# SUPPLY.net
KiCad netlist of a schematic drawn in Altium Designer
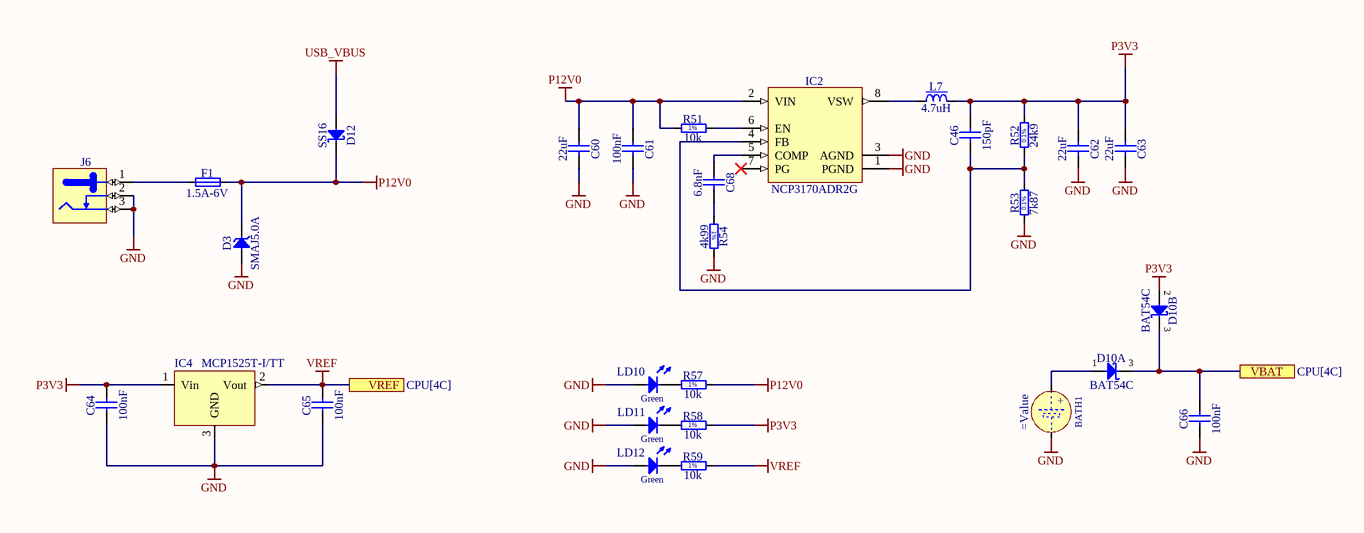
[diagram p0: SUPPLY.SchDoc]

(export (version "E")
  (design (tool "Eeschema 10.0.6"))
  (components
    (comp (ref "BATH1")
      (value "~")
      (footprint "BATH_KEYSTONE_2998")
      (description "Battery Holder whit 2 Pin")
      (fields
        (field (name "PART NUMBER") "BATH_KEYSTONE_2998")
        (field (name "MANUFACTURER") "KEYSTONE")
        (field (name "AUTHOR") "CERN DEM JLC")
      )
      (libsource (lib "Eletro-mechanical") (part "Battery Holder 2 Pin"))
    )
    (comp (ref "C46")
      (value "150pF")
      (footprint "CAPC1005X55N")
      (description "Non-polarised capacitor")
      (fields
        (field (name "PART NUMBER") "CC0402_150PF_50V_5%_C0G")
        (field (name "VOLTAGE") "50V")
        (field (name "AUTHOR") "CERN DEM JLC")
      )
      (libsource (lib "Capacitors") (part "Capacitor - non polarized"))
    )
    (comp (ref "C60")
      (value "22uF")
      (footprint "CAPC2012X135N")
      (description "Non-polarised capacitor")
      (fields
        (field (name "PART NUMBER") "CC0805_22UF_16V_10%_X5R")
        (field (name "VOLTAGE") "16V")
        (field (name "AUTHOR") "CERN DEM JLC")
      )
      (libsource (lib "Capacitors") (part "Capacitor - non polarized"))
    )
    (comp (ref "C61")
      (value "100nF")
      (footprint "CAPC1005X55N")
      (description "Non-polarised capacitor")
      (fields
        (field (name "PART NUMBER") "CC0402_100NF_16V_10%_X5R")
        (field (name "VOLTAGE") "16V")
        (field (name "AUTHOR") "CERN DEM JLC")
      )
      (libsource (lib "Capacitors") (part "Capacitor - non polarized"))
    )
    (comp (ref "C62")
      (value "22uF")
      (footprint "CAPC2012X135N")
      (description "Non-polarised capacitor")
      (fields
        (field (name "PART NUMBER") "CC0805_22UF_16V_10%_X5R")
        (field (name "VOLTAGE") "16V")
        (field (name "AUTHOR") "CERN DEM JLC")
      )
      (libsource (lib "Capacitors") (part "Capacitor - non polarized"))
    )
    (comp (ref "C63")
      (value "22uF")
      (footprint "CAPC2012X135N")
      (description "Non-polarised capacitor")
      (fields
        (field (name "PART NUMBER") "CC0805_22UF_16V_10%_X5R")
        (field (name "VOLTAGE") "16V")
        (field (name "AUTHOR") "CERN DEM JLC")
      )
      (libsource (lib "Capacitors") (part "Capacitor - non polarized"))
    )
    (comp (ref "C64")
      (value "100nF")
      (footprint "CAPC1005X55N")
      (description "Non-polarised capacitor")
      (fields
        (field (name "PART NUMBER") "CC0402_100NF_16V_10%_X5R")
        (field (name "VOLTAGE") "16V")
        (field (name "AUTHOR") "CERN DEM JLC")
      )
      (libsource (lib "Capacitors") (part "Capacitor - non polarized"))
    )
    (comp (ref "C65")
      (value "100nF")
      (footprint "CAPC1005X55N")
      (description "Non-polarised capacitor")
      (fields
        (field (name "PART NUMBER") "CC0402_100NF_16V_10%_X5R")
        (field (name "VOLTAGE") "16V")
        (field (name "AUTHOR") "CERN DEM JLC")
      )
      (libsource (lib "Capacitors") (part "Capacitor - non polarized"))
    )
    (comp (ref "C66")
      (value "100nF")
      (footprint "CAPC1005X55N")
      (description "Non-polarised capacitor")
      (fields
        (field (name "PART NUMBER") "CC0402_100NF_16V_10%_X5R")
        (field (name "VOLTAGE") "16V")
        (field (name "AUTHOR") "CERN DEM JLC")
      )
      (libsource (lib "Capacitors") (part "Capacitor - non polarized"))
    )
    (comp (ref "C68")
      (value "6.8nF")
      (footprint "CAPC1608X87N")
      (description "Non-polarised capacitor")
      (fields
        (field (name "PART NUMBER") "CC0603_6.8NF_50V_5%_X7R")
        (field (name "VOLTAGE") "50V")
        (field (name "AUTHOR") "CERN DEM JLC")
      )
      (libsource (lib "Capacitors") (part "Capacitor - non polarized"))
    )
    (comp (ref "D3")
      (value "SMAJ5.0A")
      (footprint "DIOM5226X262N")
      (description "Transient Voltage Suppressor Diode (Uni-Directional)")
      (fields
        (field (name "VOLTAGE") "5V")
        (field (name "POWER") "400W")
        (field (name "AUTHOR") "CERN DEM MR")
      )
      (libsource (lib "ICs And Semiconductors") (part "Diode TVS Uni-Directional"))
    )
    (comp (ref "D10")
      (value "BAT54C")
      (footprint "SOT95P240X130-3N")
      (description "Dual Common Cathode Schottky Diodes")
      (fields
        (field (name "VOLTAGE") "30V")
        (field (name "POWER") "200mA")
        (field (name "AUTHOR") "CERN DEM JLC")
      )
      (libsource (lib "ICs And Semiconductors") (part "Diode Schottky x2 A1C3_A2C3"))
    )
    (comp (ref "D12")
      (value "SS16")
      (footprint "DIOM5127X229N")
      (description "Schottky Diode")
      (fields
        (field (name "VOLTAGE") "60V")
        (field (name "POWER") "1A")
        (field (name "AUTHOR") "CERN DEM JLC")
      )
      (libsource (lib "ICs And Semiconductors") (part "Diode Schottky"))
    )
    (comp (ref "F1")
      (value "1.5A-6V")
      (footprint "FUSRC4632X90N")
      (description "Fuse")
      (fields
        (field (name "PART NUMBER") "FUSR1812_TYCO-MINISMDC150F-2")
        (field (name "MANUFACTURER") "TYCO ELECTRONICS")
        (field (name "AUTHOR") "CERN DEM MR")
      )
      (libsource (lib "Eletro-mechanical") (part "Fuse"))
    )
    (comp (ref "IC2")
      (value "NCP3170ADR2G")
      (footprint "SOIC127P600X175-8N")
      (description "Synchronous PWM Switching Converter")
      (fields (field (name "MANUFACTURER") "ON SEMICONDUCTOR") (field (name "AUTHOR") "CERN DEM MR"))
      (libsource (lib "ICs And Semiconductors") (part "NCP3170ADR2G"))
    )
    (comp (ref "IC4")
      (value "MCP1525T-I/TT")
      (footprint "SOT95P251X112-3N")
      (description "2.5 voltage reference")
      (libsource (lib "LIBRARY_SCH") (part "REF_MCP1525"))
    )
    (comp (ref "J6")
      (value "Jack")
      (footprint "CLIFF_FC68148(DC-10A)")
      (description "12V /  5A, 2.1mm Diameter Pin, DC Power Socket With  Switch. DC10A Type")
      (fields
        (field (name "PART NUMBER") "CLIFF_FC68148(DC-10A)")
        (field (name "MANUFACTURER") "CLIFF ELECTRONIC COMPONENTS")
        (field (name "AUTHOR") "CERN DEM JLC")
      )
      (libsource (lib "Connectors") (part "CLIFF_FC68148(DC-10A)"))
    )
    (comp (ref "L7")
      (value "4.7uH")
      (footprint "INDM5552X200N")
      (description "Inductor With Core")
      (fields
        (field (name "PART NUMBER") "IND2020_4.7UH_20%_VISHAY_IHLP-2020BZ-11")
        (field (name "POWER") "3.2A")
        (field (name "AUTHOR") "CERN DEM JLC")
      )
      (libsource (lib "Inductors & Transformers") (part "Inductor With Magnetic core"))
    )
    (comp (ref "LD10")
      (value "~")
      (footprint "LED_OSRAM_LGL29K")
      (description "LED Green 1C 2A")
      (fields
        (field (name "PART NUMBER") "LED_OSRAM_LG L29K-G2J1-24-Z")
        (field (name "MANUFACTURER") "OSRAM")
        (field (name "AUTHOR") "CERN DEM JLC")
      )
      (libsource (lib "ICs And Semiconductors") (part "LED Green 1C 2A"))
    )
    (comp (ref "LD11")
      (value "~")
      (footprint "LED_OSRAM_LGL29K")
      (description "LED Green 1C 2A")
      (fields
        (field (name "PART NUMBER") "LED_OSRAM_LG L29K-G2J1-24-Z")
        (field (name "MANUFACTURER") "OSRAM")
        (field (name "AUTHOR") "CERN DEM JLC")
      )
      (libsource (lib "ICs And Semiconductors") (part "LED Green 1C 2A"))
    )
    (comp (ref "LD12")
      (value "~")
      (footprint "LED_OSRAM_LGL29K")
      (description "LED Green 1C 2A")
      (fields
        (field (name "PART NUMBER") "LED_OSRAM_LG L29K-G2J1-24-Z")
        (field (name "MANUFACTURER") "OSRAM")
        (field (name "AUTHOR") "CERN DEM JLC")
      )
      (libsource (lib "ICs And Semiconductors") (part "LED Green 1C 2A"))
    )
    (comp (ref "R51")
      (value "10k")
      (footprint "RESC1005X40N")
      (description "Resistor - 1%")
      (fields
        (field (name "PART NUMBER") "R0402_10K_1%_0.0625W_100PPM")
        (field (name "POWER") "0.0625W")
        (field (name "AUTHOR") "CERN DEM JLC")
      )
      (libsource (lib "Resistors") (part "Resistor - 1%"))
    )
    (comp (ref "R52")
      (value "24k9")
      (footprint "RESC1608X55N")
      (description "Resistor - 0.1%")
      (fields
        (field (name "PART NUMBER") "R0603_24K9_0.1%_0.063W_10PPM")
        (field (name "POWER") "0.063W")
        (field (name "AUTHOR") "CERN DEM JLC")
      )
      (libsource (lib "Resistors") (part "Resistor - 0.1%"))
    )
    (comp (ref "R53")
      (value "7k87")
      (footprint "RESC1608X55N")
      (description "Resistor - 0.1%")
      (fields
        (field (name "PART NUMBER") "R0603_7K87_0.1%_0.063W_10PPM")
        (field (name "POWER") "0.063W")
        (field (name "AUTHOR") "CERN DEM JLC")
      )
      (libsource (lib "Resistors") (part "Resistor - 0.1%"))
    )
    (comp (ref "R54")
      (value "4k99")
      (footprint "RESC1608X55N")
      (description "Resistor - 1%")
      (fields
        (field (name "PART NUMBER") "R0603_4K99_1%_0.063W_50PPM")
        (field (name "POWER") "0.1W")
        (field (name "AUTHOR") "CERN DEM JLC")
      )
      (libsource (lib "Resistors") (part "Resistor - 1%"))
    )
    (comp (ref "R57")
      (value "10k")
      (footprint "RESC1005X40N")
      (description "Resistor - 1%")
      (fields
        (field (name "PART NUMBER") "R0402_10K_1%_0.0625W_100PPM")
        (field (name "POWER") "0.0625W")
        (field (name "AUTHOR") "CERN DEM JLC")
      )
      (libsource (lib "Resistors") (part "Resistor - 1%"))
    )
    (comp (ref "R58")
      (value "10k")
      (footprint "RESC1005X40N")
      (description "Resistor - 1%")
      (fields
        (field (name "PART NUMBER") "R0402_10K_1%_0.0625W_100PPM")
        (field (name "POWER") "0.0625W")
        (field (name "AUTHOR") "CERN DEM JLC")
      )
      (libsource (lib "Resistors") (part "Resistor - 1%"))
    )
    (comp (ref "R59")
      (value "10k")
      (footprint "RESC1005X40N")
      (description "Resistor - 1%")
      (fields
        (field (name "PART NUMBER") "R0402_10K_1%_0.0625W_100PPM")
        (field (name "POWER") "0.0625W")
        (field (name "AUTHOR") "CERN DEM JLC")
      )
      (libsource (lib "Resistors") (part "Resistor - 1%"))
    )
  )
  (nets
    (net (code "1") (name "/VBAT") (class "Default")
      (node (ref "C66") (pin "2") (pinfunction "2_2") (pintype "passive"))
      (node (ref "D10") (pin "3") (pinfunction "COMC_3") (pintype "passive"))
    )
    (net (code "2") (name "GND") (class "Default")
      (node (ref "BATH1") (pin "2") (pinfunction "MINUS_2") (pintype "power_in"))
      (node (ref "C60") (pin "2") (pinfunction "2_2") (pintype "passive"))
      (node (ref "C61") (pin "2") (pinfunction "2_2") (pintype "passive"))
      (node (ref "C62") (pin "2") (pinfunction "2_2") (pintype "passive"))
      (node (ref "C63") (pin "2") (pinfunction "2_2") (pintype "passive"))
      (node (ref "C64") (pin "1") (pinfunction "1_1") (pintype "passive"))
      (node (ref "C65") (pin "1") (pinfunction "1_1") (pintype "passive"))
      (node (ref "C66") (pin "1") (pinfunction "1_1") (pintype "passive"))
      (node (ref "D3") (pin "2") (pinfunction "A_2") (pintype "passive"))
      (node (ref "IC2") (pin "1") (pinfunction "PGND_1") (pintype "power_in"))
      (node (ref "IC2") (pin "3") (pinfunction "AGND_3") (pintype "power_in"))
      (node (ref "IC4") (pin "3") (pinfunction "GND_3") (pintype "power_in"))
      (node (ref "J6") (pin "2") (pinfunction "2_2") (pintype "bidirectional"))
      (node (ref "J6") (pin "3") (pinfunction "3_3") (pintype "bidirectional"))
      (node (ref "LD10") (pin "2") (pinfunction "A_2") (pintype "passive"))
      (node (ref "LD11") (pin "2") (pinfunction "A_2") (pintype "passive"))
      (node (ref "LD12") (pin "2") (pinfunction "A_2") (pintype "passive"))
      (node (ref "R53") (pin "1") (pinfunction "1_1") (pintype "passive"))
      (node (ref "R54") (pin "2") (pinfunction "2_2") (pintype "passive"))
    )
    (net (code "3") (name "Net-(BATH1-PLUS)") (class "Default")
      (node (ref "BATH1") (pin "1") (pinfunction "PLUS_1") (pintype "power_in"))
      (node (ref "D10") (pin "1") (pinfunction "A_1") (pintype "passive"))
    )
    (net (code "4") (name "Net-(C68-Pad2)") (class "Default")
      (node (ref "C68") (pin "2") (pinfunction "2_2") (pintype "passive"))
      (node (ref "R54") (pin "1") (pinfunction "1_1") (pintype "passive"))
    )
    (net (code "5") (name "Net-(F1-Pad1)") (class "Default")
      (node (ref "F1") (pin "1") (pinfunction "1_1") (pintype "passive"))
      (node (ref "J6") (pin "1") (pinfunction "1_1") (pintype "bidirectional"))
    )
    (net (code "6") (name "Net-(IC2-COMP)") (class "Default")
      (node (ref "C68") (pin "1") (pinfunction "1_1") (pintype "passive"))
      (node (ref "IC2") (pin "5") (pinfunction "COMP_5") (pintype "input"))
    )
    (net (code "7") (name "Net-(IC2-EN)") (class "Default")
      (node (ref "IC2") (pin "6") (pinfunction "EN_6") (pintype "input"))
      (node (ref "R51") (pin "2") (pinfunction "2_2") (pintype "passive"))
    )
    (net (code "8") (name "Net-(IC2-FB)") (class "Default")
      (node (ref "C46") (pin "1") (pinfunction "1_1") (pintype "passive"))
      (node (ref "IC2") (pin "4") (pinfunction "FB_4") (pintype "input"))
      (node (ref "R52") (pin "1") (pinfunction "1_1") (pintype "passive"))
      (node (ref "R53") (pin "2") (pinfunction "2_2") (pintype "passive"))
    )
    (net (code "9") (name "Net-(IC2-VSW)") (class "Default")
      (node (ref "IC2") (pin "8") (pinfunction "VSW_8") (pintype "output"))
      (node (ref "L7") (pin "1") (pinfunction "1_1") (pintype "passive"))
    )
    (net (code "10") (name "Net-(LD10-C)") (class "Default")
      (node (ref "LD10") (pin "1") (pinfunction "C_1") (pintype "passive"))
      (node (ref "R57") (pin "1") (pinfunction "1_1") (pintype "passive"))
    )
    (net (code "11") (name "Net-(LD11-C)") (class "Default")
      (node (ref "LD11") (pin "1") (pinfunction "C_1") (pintype "passive"))
      (node (ref "R58") (pin "1") (pinfunction "1_1") (pintype "passive"))
    )
    (net (code "12") (name "Net-(LD12-C)") (class "Default")
      (node (ref "LD12") (pin "1") (pinfunction "C_1") (pintype "passive"))
      (node (ref "R59") (pin "1") (pinfunction "1_1") (pintype "passive"))
    )
    (net (code "13") (name "P3V3") (class "Default")
      (node (ref "C46") (pin "2") (pinfunction "2_2") (pintype "passive"))
      (node (ref "C62") (pin "1") (pinfunction "1_1") (pintype "passive"))
      (node (ref "C63") (pin "1") (pinfunction "1_1") (pintype "passive"))
      (node (ref "C64") (pin "2") (pinfunction "2_2") (pintype "passive"))
      (node (ref "D10") (pin "2") (pinfunction "A_2") (pintype "passive"))
      (node (ref "IC4") (pin "1") (pinfunction "Vin_1") (pintype "power_in"))
      (node (ref "L7") (pin "2") (pinfunction "2_2") (pintype "passive"))
      (node (ref "R52") (pin "2") (pinfunction "2_2") (pintype "passive"))
      (node (ref "R58") (pin "2") (pinfunction "2_2") (pintype "passive"))
    )
    (net (code "14") (name "P12V0") (class "Default")
      (node (ref "C60") (pin "1") (pinfunction "1_1") (pintype "passive"))
      (node (ref "C61") (pin "1") (pinfunction "1_1") (pintype "passive"))
      (node (ref "D12") (pin "1") (pinfunction "C_1") (pintype "passive"))
      (node (ref "D3") (pin "1") (pinfunction "C_1") (pintype "passive"))
      (node (ref "F1") (pin "2") (pinfunction "2_2") (pintype "passive"))
      (node (ref "IC2") (pin "2") (pinfunction "VIN_2") (pintype "input"))
      (node (ref "R51") (pin "1") (pinfunction "1_1") (pintype "passive"))
      (node (ref "R57") (pin "2") (pinfunction "2_2") (pintype "passive"))
    )
    (net (code "15") (name "USB_VBUS") (class "Default")
      (node (ref "D12") (pin "2") (pinfunction "A_2") (pintype "passive"))
    )
    (net (code "16") (name "VREF") (class "Default")
      (node (ref "C65") (pin "2") (pinfunction "2_2") (pintype "passive"))
      (node (ref "IC4") (pin "2") (pinfunction "Vout_2") (pintype "output"))
      (node (ref "R59") (pin "2") (pinfunction "2_2") (pintype "passive"))
    )
    (net (code "17") (name "unconnected-(IC2-PG-Pad7)") (class "Default")
      (node (ref "IC2") (pin "7") (pinfunction "PG_7") (pintype "input+no_connect"))
    )
  )
)
